# amc7135-testboard-mk-1_0.net
KiCad netlist of a schematic drawn in EAGLE
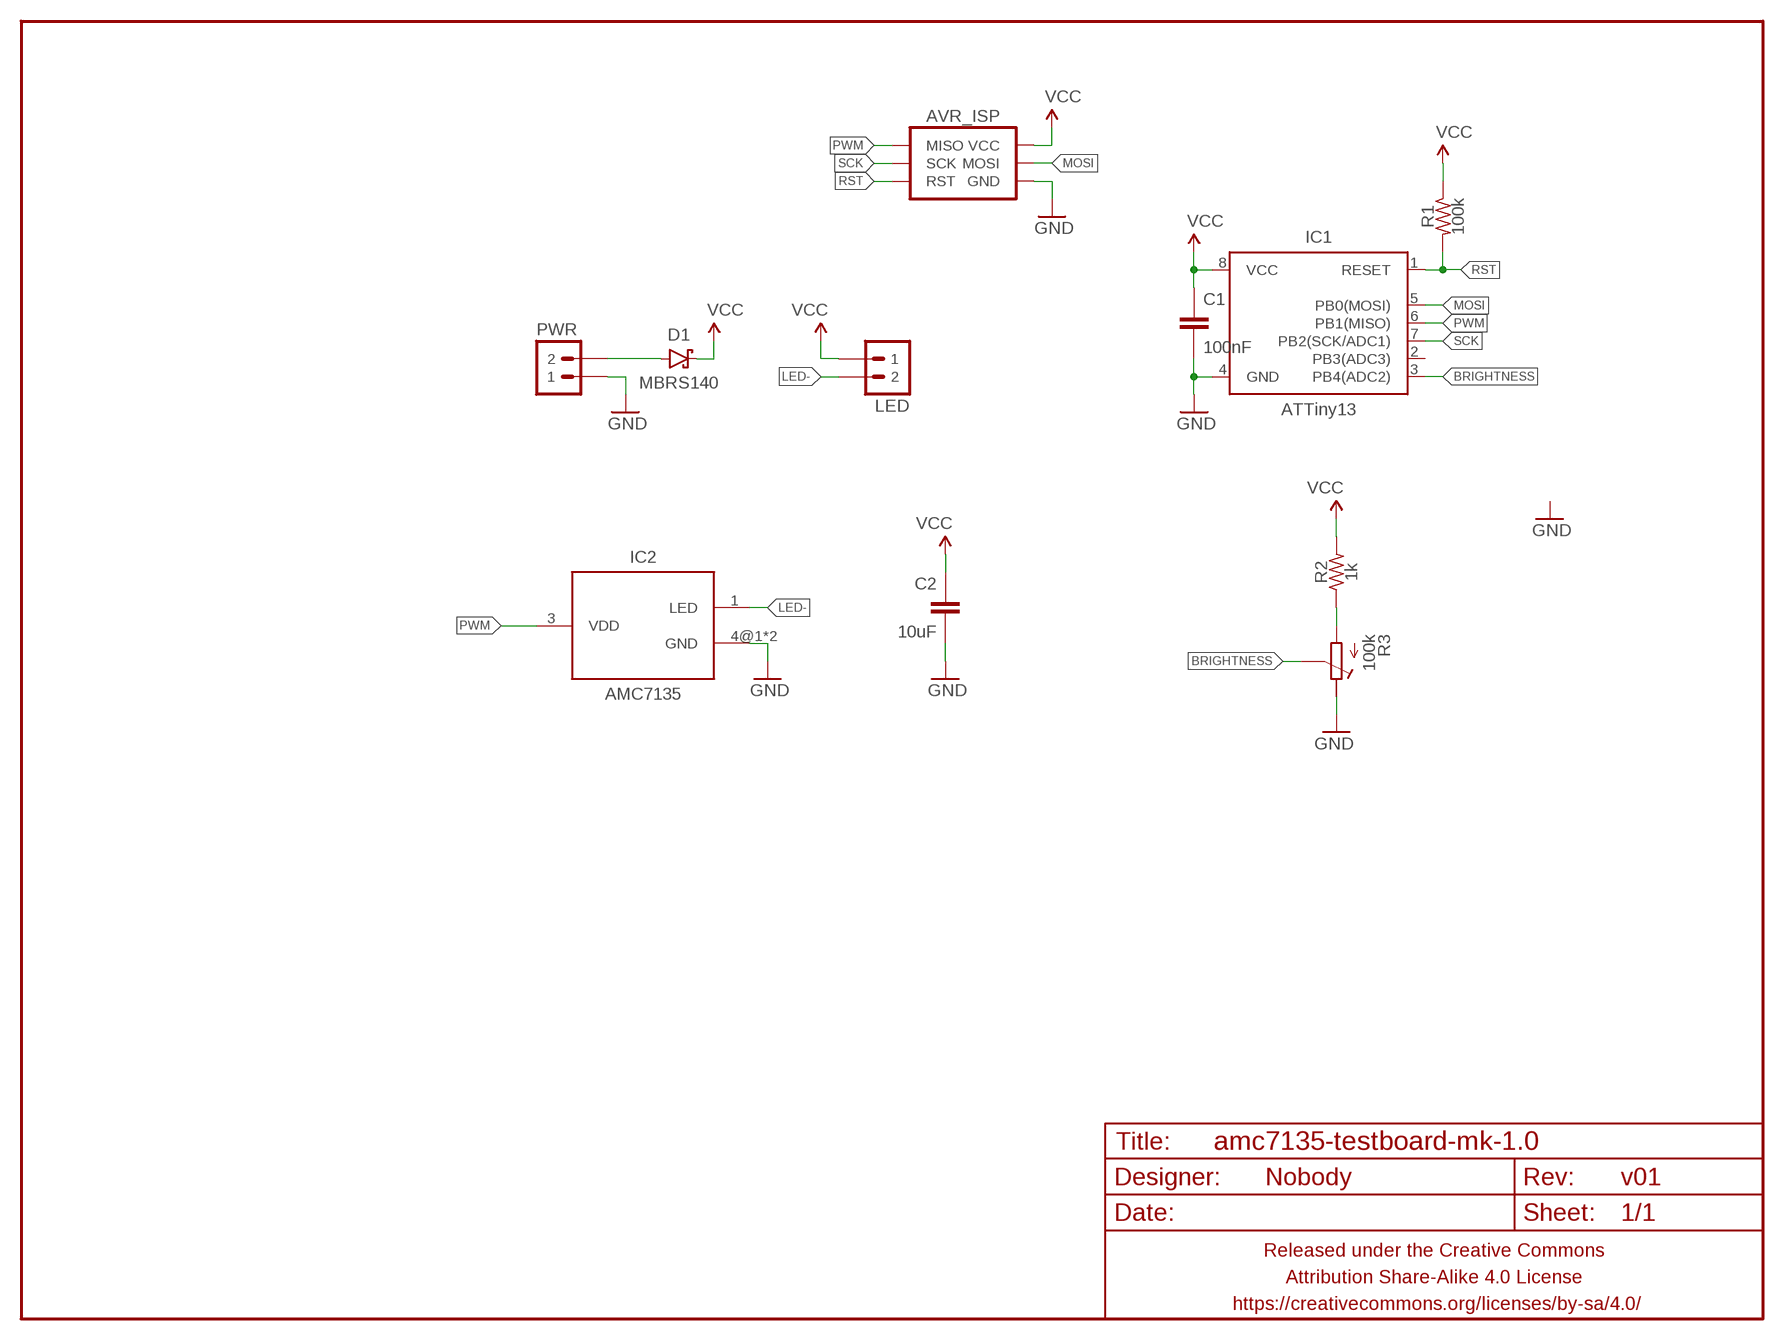
[diagram p0: schematic, sheet 1]

(export (version "E")
  (design (tool "Eeschema 10.0.6"))
  (components
    (comp (ref "AVR_ISP")
      (value "AVR_SPI_PRG_6SMD_TEST_POINTS")
      (footprint "eagle-import:2X3_SMD_TEST_POINTS")
      (libsource (lib "eagle-import") (part "AVR_SPI_PRG_6SMD_TEST_POINTS"))
    )
    (comp (ref "C1")
      (value "100nF")
      (footprint "eagle-import:C0805")
      (libsource (lib "eagle-import") (part "CAPACITOR-CERAMICC0805"))
    )
    (comp (ref "C2")
      (value "10uF")
      (footprint "eagle-import:C0805")
      (libsource (lib "eagle-import") (part "CAPACITOR-CERAMICC0805"))
    )
    (comp (ref "D1")
      (value "MBRS140")
      (footprint "eagle-import:SMA-DIODE-SCHOTTKY")
      (libsource (lib "eagle-import") (part "DIODE-SCHOTTKYSMA"))
    )
    (comp (ref "FRAME1")
      (value "FRAME-LETTERNO_PACKAGE")
      (footprint "eagle-import:DUMMY")
      (fields (field (name "DESIGNER") "Nobody"))
      (libsource (lib "eagle-import") (part "FRAME-LETTERNO_PACKAGE"))
    )
    (comp (ref "IC1")
      (value "ATTiny13")
      (footprint "eagle-import:SO08")
      (libsource (lib "eagle-import") (part "ATTINY13SOIC"))
    )
    (comp (ref "IC2")
      (value "AMC7135")
      (footprint "eagle-import:SOT89-NOTHERM")
      (libsource (lib "eagle-import") (part "AMC7135SOT-89-NOTHERM"))
    )
    (comp (ref "LED")
      (value "M02JST-PTH-RA-SMALLPADS")
      (footprint "eagle-import:JST-2-PH-RA-PTH-SMALLPADS")
      (libsource (lib "eagle-import") (part "M02JST-PTH-RA-SMALLPADS"))
    )
    (comp (ref "PWR")
      (value "M02JST-PTH-RA-SMALLPADS")
      (footprint "eagle-import:JST-2-PH-RA-PTH-SMALLPADS")
      (libsource (lib "eagle-import") (part "M02JST-PTH-RA-SMALLPADS"))
    )
    (comp (ref "R1")
      (value "100k")
      (footprint "eagle-import:R0805")
      (libsource (lib "eagle-import") (part "RESISTORR0805"))
    )
    (comp (ref "R2")
      (value "1k")
      (footprint "eagle-import:R0805")
      (libsource (lib "eagle-import") (part "RESISTORR0805"))
    )
    (comp (ref "R3")
      (value "100k")
      (footprint "eagle-import:EVM3Y")
      (libsource (lib "eagle-import") (part "POTENTIOMETEREVM3Y"))
    )
  )
  (nets
    (net (code "1") (name "BRIGHTNESS") (class "Default")
      (node (ref "IC1") (pin "3") (pinfunction "PB4(ADC2)_3") (pintype "bidirectional"))
      (node (ref "R3") (pin "S") (pinfunction "S_S") (pintype "passive"))
    )
    (net (code "2") (name "GND") (class "Default")
      (node (ref "AVR_ISP") (pin "6") (pinfunction "GND_6") (pintype "passive"))
      (node (ref "C1") (pin "2") (pinfunction "2_2") (pintype "passive"))
      (node (ref "C2") (pin "2") (pinfunction "2_2") (pintype "passive"))
      (node (ref "IC1") (pin "4") (pinfunction "GND_4") (pintype "bidirectional"))
      (node (ref "IC2") (pin "4@1") (pinfunction "GND_4@1") (pintype "bidirectional"))
      (node (ref "IC2") (pin "4@2") (pinfunction "GND_4@2") (pintype "bidirectional"))
      (node (ref "PWR") (pin "1") (pinfunction "1_1") (pintype "passive"))
      (node (ref "R3") (pin "E") (pinfunction "E_E") (pintype "passive"))
    )
    (net (code "3") (name "LED-") (class "Default")
      (node (ref "IC2") (pin "1") (pinfunction "LED_1") (pintype "bidirectional"))
      (node (ref "LED") (pin "2") (pinfunction "2_2") (pintype "passive"))
    )
    (net (code "4") (name "MOSI") (class "Default")
      (node (ref "AVR_ISP") (pin "4") (pinfunction "MOSI_4") (pintype "passive"))
      (node (ref "IC1") (pin "5") (pinfunction "PB0(MOSI)_5") (pintype "bidirectional"))
    )
    (net (code "5") (name "Net-(D1-PadA)") (class "Default")
      (node (ref "D1") (pin "A") (pinfunction "A_A") (pintype "passive"))
      (node (ref "PWR") (pin "2") (pinfunction "2_2") (pintype "passive"))
    )
    (net (code "6") (name "Net-(R2-Pad1)") (class "Default")
      (node (ref "R2") (pin "1") (pinfunction "1_1") (pintype "passive"))
      (node (ref "R3") (pin "A") (pinfunction "A_A") (pintype "passive"))
    )
    (net (code "7") (name "PWM") (class "Default")
      (node (ref "AVR_ISP") (pin "1") (pinfunction "MISO_1") (pintype "passive"))
      (node (ref "IC1") (pin "6") (pinfunction "PB1(MISO)_6") (pintype "bidirectional"))
      (node (ref "IC2") (pin "3") (pinfunction "VDD_3") (pintype "bidirectional"))
    )
    (net (code "8") (name "RST") (class "Default")
      (node (ref "AVR_ISP") (pin "5") (pinfunction "RST_5") (pintype "passive"))
      (node (ref "IC1") (pin "1") (pinfunction "RESET_1") (pintype "bidirectional"))
      (node (ref "R1") (pin "2") (pinfunction "2_2") (pintype "passive"))
    )
    (net (code "9") (name "SCK") (class "Default")
      (node (ref "AVR_ISP") (pin "3") (pinfunction "SCK_3") (pintype "passive"))
      (node (ref "IC1") (pin "7") (pinfunction "PB2(SCK/ADC1)_7") (pintype "bidirectional"))
    )
    (net (code "10") (name "VCC") (class "Default")
      (node (ref "AVR_ISP") (pin "2") (pinfunction "VCC_2") (pintype "passive"))
      (node (ref "C1") (pin "1") (pinfunction "1_1") (pintype "passive"))
      (node (ref "C2") (pin "1") (pinfunction "1_1") (pintype "passive"))
      (node (ref "D1") (pin "C") (pinfunction "C_C") (pintype "passive"))
      (node (ref "IC1") (pin "8") (pinfunction "VCC_8") (pintype "bidirectional"))
      (node (ref "LED") (pin "1") (pinfunction "1_1") (pintype "passive"))
      (node (ref "R1") (pin "1") (pinfunction "1_1") (pintype "passive"))
      (node (ref "R2") (pin "2") (pinfunction "2_2") (pintype "passive"))
    )
    (net (code "11") (name "unconnected-(IC1-PB3(ADC3)-Pad2)") (class "Default")
      (node (ref "IC1") (pin "2") (pinfunction "PB3(ADC3)_2") (pintype "bidirectional"))
    )
  )
)
